# Power_Supply_Board.net
KiCad netlist of a schematic drawn in EasyEDA Pro
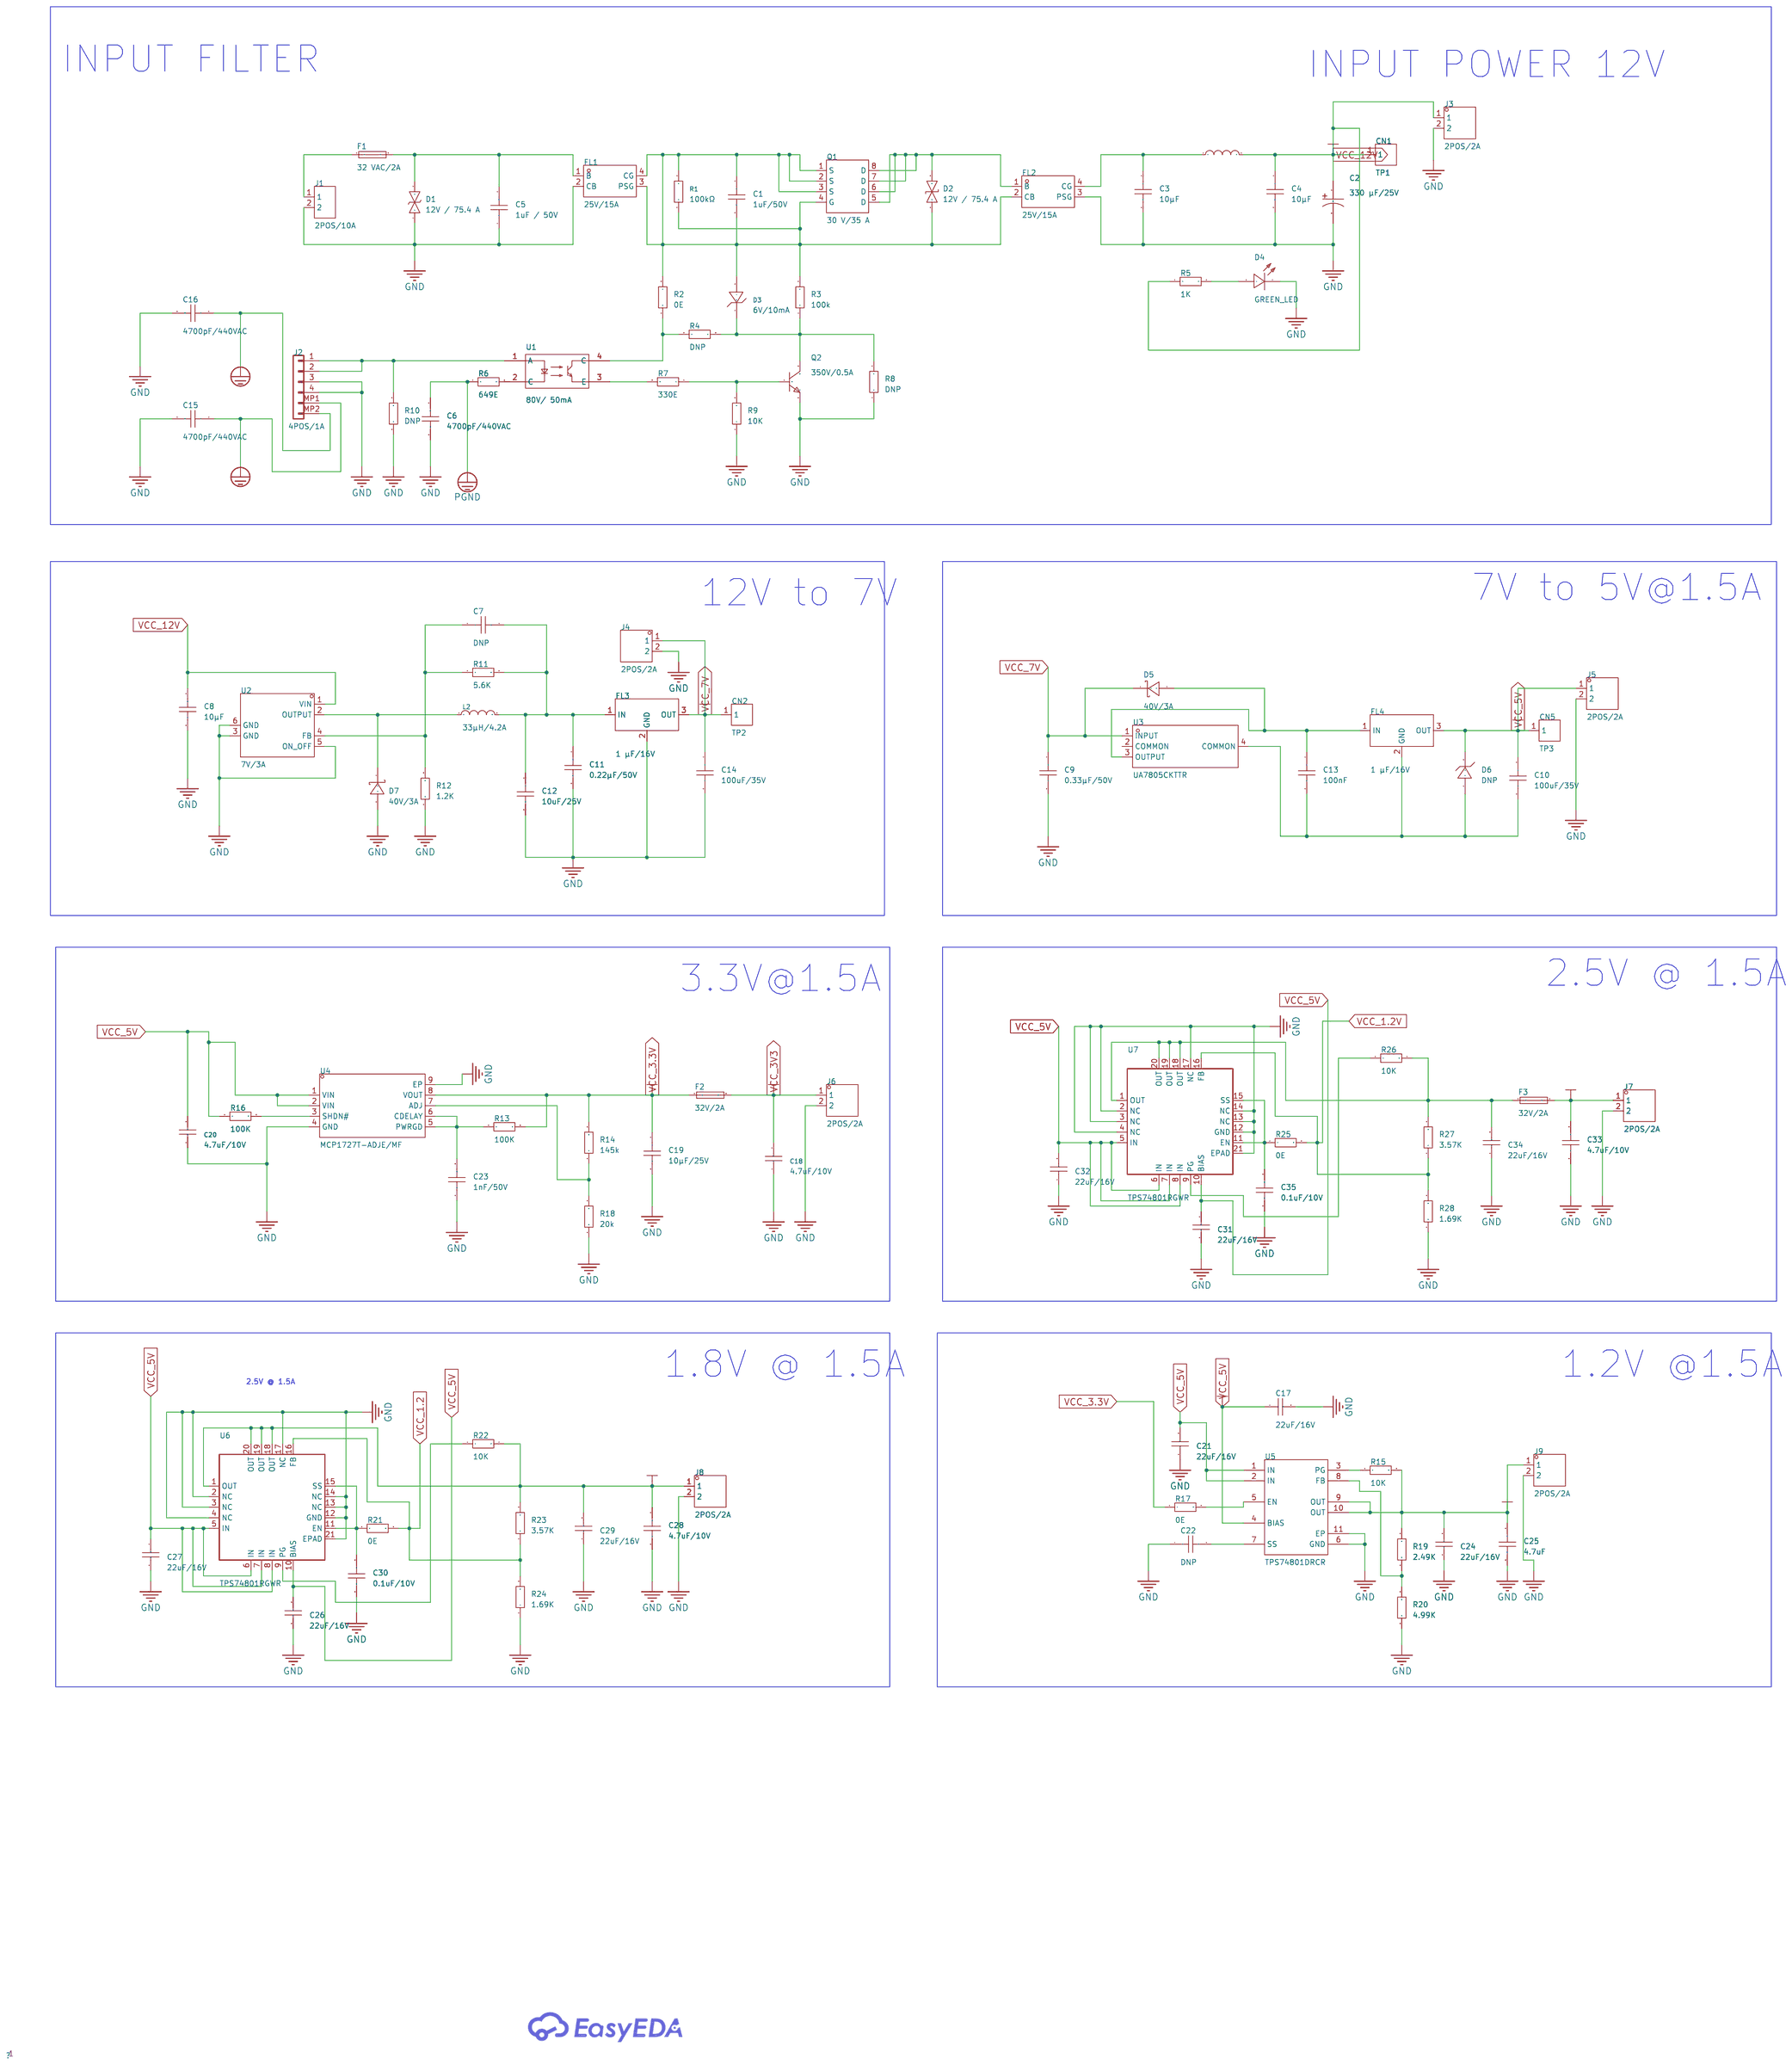
[diagram p0: schematic sheet]

(export (version "E")
  (design (tool "Eeschema 10.0.6"))
  (components
    (comp (ref "C1")
      (value "1uF/50V")
      (footprint "easyedapro:C0603")
      (libsource (lib "easyedapro") (part "CAP"))
    )
    (comp (ref "C2")
      (value "330 µF/25V")
      (footprint "easyedapro:CAP-SMD_BD10.0-L10.3-W10.3-FD")
      (fields (field (name "Manufacturer Part") "EEHZA1E331P") (field (name "Manufacturer") "PANASONIC(松下)"))
      (libsource (lib "easyedapro") (part "EEHZA1E331P"))
    )
    (comp (ref "C3")
      (value "10µF")
      (footprint "easyedapro:C0603")
      (libsource (lib "easyedapro") (part "CAP"))
    )
    (comp (ref "C4")
      (value "10µF")
      (footprint "easyedapro:C0603")
      (libsource (lib "easyedapro") (part "CAP"))
    )
    (comp (ref "C5")
      (value "1uF / 50V")
      (footprint "easyedapro:C0402")
      (description "Capacitance:100nF Tolerance:±10% Tolerance:±10% Voltage Rating:16V Temperature Coefficient:X7R")
      (fields
        (field (name "Manufacturer Part") "CL05B104KO5NNNC")
        (field (name "Manufacturer") "SAMSUNG(三星)")
      )
      (libsource (lib "easyedapro") (part "CL05B104KO5NNNC"))
    )
    (comp (ref "C6")
      (value "4700pF/440VAC")
      (footprint "easyedapro:CAP-TH_L11.0-W5.0-P10.00-D0.7")
      (fields
        (field (name "Manufacturer Part") "C947U472MZVDBA7317")
        (field (name "Manufacturer") "KEMET(基美)")
      )
      (libsource (lib "easyedapro") (part "C947U472MZVDBA7317"))
    )
    (comp (ref "C7") (value "DNP") (footprint "easyedapro:C0603") (libsource (lib "easyedapro") (part "CAP")))
    (comp (ref "C8")
      (value "10µF")
      (footprint "easyedapro:C0603")
      (libsource (lib "easyedapro") (part "CAP"))
    )
    (comp (ref "C9")
      (value "0.33µF/50V")
      (footprint "easyedapro:C0603")
      (libsource (lib "easyedapro") (part "CAP"))
    )
    (comp (ref "C10")
      (value "100uF/35V")
      (footprint "easyedapro:C0603")
      (libsource (lib "easyedapro") (part "CAP"))
    )
    (comp (ref "C11")
      (value "0.22µF/50V")
      (footprint "easyedapro:C0603")
      (libsource (lib "easyedapro") (part "CAP"))
    )
    (comp (ref "C12")
      (value "10uF/25V")
      (footprint "easyedapro:C0603")
      (libsource (lib "easyedapro") (part "CAP"))
    )
    (comp (ref "C13")
      (value "100nF")
      (footprint "easyedapro:C0603")
      (libsource (lib "easyedapro") (part "CAP"))
    )
    (comp (ref "C14")
      (value "100uF/35V")
      (footprint "easyedapro:C0603")
      (libsource (lib "easyedapro") (part "CAP"))
    )
    (comp (ref "C15")
      (value "4700pF/440VAC")
      (footprint "easyedapro:C0603")
      (libsource (lib "easyedapro") (part "CAP"))
    )
    (comp (ref "C16")
      (value "4700pF/440VAC")
      (footprint "easyedapro:C0603")
      (libsource (lib "easyedapro") (part "CAP"))
    )
    (comp (ref "C17")
      (value "22uF/16V")
      (footprint "easyedapro:C0805")
      (description "容值:22uF;精度:±20%;额定电压:16V;材质(温度系数):X5R;")
      (fields
        (field (name "Manufacturer Part") "CL21A226MOQNNNE")
        (field (name "Manufacturer") "SAMSUNG(三星)")
      )
      (libsource (lib "easyedapro") (part "CL21A226MOQNNNE"))
    )
    (comp (ref "C18")
      (value "4.7uF/10V")
      (footprint "easyedapro:C0603")
      (description "Capacitance:4.7uF Tolerance:±10% Tolerance:±10% Voltage Rating:10V Temperature Coefficient:X5R")
      (fields
        (field (name "Manufacturer Part") "CL10A475KP8NNNC")
        (field (name "Manufacturer") "SAMSUNG(三星)")
      )
      (libsource (lib "easyedapro") (part "CL10A475KP8NNNC"))
    )
    (comp (ref "C19")
      (value "10µF/25V")
      (footprint "easyedapro:C0603")
      (libsource (lib "easyedapro") (part "CAP"))
    )
    (comp (ref "C20")
      (value "4.7uF/10V")
      (footprint "easyedapro:C0603")
      (description "Capacitance:4.7uF Tolerance:±10% Tolerance:±10% Voltage Rating:10V Temperature Coefficient:X5R")
      (fields
        (field (name "Manufacturer Part") "CL10A475KP8NNNC")
        (field (name "Manufacturer") "SAMSUNG(三星)")
      )
      (libsource (lib "easyedapro") (part "CL10A475KP8NNNC"))
    )
    (comp (ref "C21")
      (value "22uF/16V")
      (footprint "easyedapro:C0805")
      (description "容值:22uF;精度:±20%;额定电压:16V;材质(温度系数):X5R;")
      (fields
        (field (name "Manufacturer Part") "CL21A226MOQNNNE")
        (field (name "Manufacturer") "SAMSUNG(三星)")
      )
      (libsource (lib "easyedapro") (part "CL21A226MOQNNNE"))
    )
    (comp (ref "C22")
      (value "DNP")
      (footprint "easyedapro:C0402")
      (fields
        (field (name "Manufacturer Part") "CC0402JRX7R6BB104")
        (field (name "Manufacturer") "YAGEO(国巨)")
      )
      (libsource (lib "easyedapro") (part "CC0402JRX7R6BB104"))
    )
    (comp (ref "C23")
      (value "1nF/50V")
      (footprint "easyedapro:C0402")
      (description "Capacitance:1nF Tolerance:±5% Tolerance:±5% Voltage Rating:50V Temperature Coefficient:C0G")
      (fields
        (field (name "Manufacturer Part") "GRM1555C1H102JA01D")
        (field (name "Manufacturer") "muRata(村田)")
      )
      (libsource (lib "easyedapro") (part "GRM1555C1H102JA01D"))
    )
    (comp (ref "C24")
      (value "22uF/16V")
      (footprint "easyedapro:C0805")
      (description "容值:22uF;精度:±20%;额定电压:16V;材质(温度系数):X5R;")
      (fields
        (field (name "Manufacturer Part") "CL21A226MOQNNNE")
        (field (name "Manufacturer") "SAMSUNG(三星)")
      )
      (libsource (lib "easyedapro") (part "CL21A226MOQNNNE"))
    )
    (comp (ref "C25")
      (value "4.7uF")
      (footprint "easyedapro:C0603")
      (libsource (lib "easyedapro") (part "CAP"))
    )
    (comp (ref "C26")
      (value "22uF/16V")
      (footprint "easyedapro:C0805")
      (description "容值:22uF;精度:±20%;额定电压:16V;材质(温度系数):X5R;")
      (fields
        (field (name "Manufacturer Part") "CL21A226MOQNNNE")
        (field (name "Manufacturer") "SAMSUNG(三星)")
      )
      (libsource (lib "easyedapro") (part "CL21A226MOQNNNE"))
    )
    (comp (ref "C27")
      (value "22uF/16V")
      (footprint "easyedapro:C0805")
      (description "容值:22uF;精度:±20%;额定电压:16V;材质(温度系数):X5R;")
      (fields
        (field (name "Manufacturer Part") "CL21A226MOQNNNE")
        (field (name "Manufacturer") "SAMSUNG(三星)")
      )
      (libsource (lib "easyedapro") (part "CL21A226MOQNNNE"))
    )
    (comp (ref "C28")
      (value "4.7uF/10V")
      (footprint "easyedapro:C0603")
      (libsource (lib "easyedapro") (part "CAP"))
    )
    (comp (ref "C29")
      (value "22uF/16V")
      (footprint "easyedapro:C0805")
      (description "容值:22uF;精度:±20%;额定电压:16V;材质(温度系数):X5R;")
      (fields
        (field (name "Manufacturer Part") "CL21A226MOQNNNE")
        (field (name "Manufacturer") "SAMSUNG(三星)")
      )
      (libsource (lib "easyedapro") (part "CL21A226MOQNNNE"))
    )
    (comp (ref "C30")
      (value "0.1uF/10V")
      (footprint "easyedapro:C0402")
      (fields
        (field (name "Manufacturer Part") "CC0402JRX7R6BB104")
        (field (name "Manufacturer") "YAGEO(国巨)")
      )
      (libsource (lib "easyedapro") (part "CC0402JRX7R6BB104"))
    )
    (comp (ref "C31")
      (value "22uF/16V")
      (footprint "easyedapro:C0805")
      (description "容值:22uF;精度:±20%;额定电压:16V;材质(温度系数):X5R;")
      (fields
        (field (name "Manufacturer Part") "CL21A226MOQNNNE")
        (field (name "Manufacturer") "SAMSUNG(三星)")
      )
      (libsource (lib "easyedapro") (part "CL21A226MOQNNNE"))
    )
    (comp (ref "C32")
      (value "22uF/16V")
      (footprint "easyedapro:C0805")
      (description "容值:22uF;精度:±20%;额定电压:16V;材质(温度系数):X5R;")
      (fields
        (field (name "Manufacturer Part") "CL21A226MOQNNNE")
        (field (name "Manufacturer") "SAMSUNG(三星)")
      )
      (libsource (lib "easyedapro") (part "CL21A226MOQNNNE"))
    )
    (comp (ref "C33")
      (value "4.7uF/10V")
      (footprint "easyedapro:C0603")
      (libsource (lib "easyedapro") (part "CAP"))
    )
    (comp (ref "C34")
      (value "22uF/16V")
      (footprint "easyedapro:C0805")
      (description "容值:22uF;精度:±20%;额定电压:16V;材质(温度系数):X5R;")
      (fields
        (field (name "Manufacturer Part") "CL21A226MOQNNNE")
        (field (name "Manufacturer") "SAMSUNG(三星)")
      )
      (libsource (lib "easyedapro") (part "CL21A226MOQNNNE"))
    )
    (comp (ref "C35")
      (value "0.1uF/10V")
      (footprint "easyedapro:C0402")
      (fields
        (field (name "Manufacturer Part") "CC0402JRX7R6BB104")
        (field (name "Manufacturer") "YAGEO(国巨)")
      )
      (libsource (lib "easyedapro") (part "CC0402JRX7R6BB104"))
    )
    (comp (ref "CN1")
      (value "TP1")
      (footprint "easyedapro:CONN-SMD_5017")
      (libsource (lib "easyedapro") (part "5017_C9900015874"))
    )
    (comp (ref "CN2")
      (value "TP2")
      (footprint "easyedapro:CONN-SMD_5017")
      (libsource (lib "easyedapro") (part "5017_C9900015874"))
    )
    (comp (ref "CN5")
      (value "TP3")
      (footprint "easyedapro:CONN-SMD_5017")
      (libsource (lib "easyedapro") (part "5017_C9900015874"))
    )
    (comp (ref "D1")
      (value "12V / 75.4 A")
      (footprint "easyedapro:D0402-BI")
      (fields (field (name "Manufacturer") "GOOD-ARK(固锝)"))
      (libsource (lib "easyedapro") (part "GSEPD15B0005"))
    )
    (comp (ref "D2")
      (value "12V / 75.4 A")
      (footprint "easyedapro:SMC_L6.9-W5.9-LS7.9-BI")
      (fields (field (name "Manufacturer") "R+O(宏嘉诚)"))
      (libsource (lib "easyedapro") (part "SMCJ12CA_C41411748"))
    )
    (comp (ref "D3")
      (value "6V/10mA")
      (footprint "easyedapro:SOD-123_L2.7-W1.6-LS3.7-RD")
      (fields (field (name "Manufacturer") "onsemi(安森美)"))
      (libsource (lib "easyedapro") (part "MMSZ5233BT1G"))
    )
    (comp (ref "D4")
      (value "GREEN_LED")
      (footprint "easyedapro:LED0603-RD")
      (fields (field (name "Manufacturer") "LITEON(光宝)"))
      (libsource (lib "easyedapro") (part "LTST-C190KGKT"))
    )
    (comp (ref "D5")
      (value "40V/3A")
      (footprint "easyedapro:SOD-128_L3.7-W2.5-LS4.7-RD")
      (fields (field (name "Manufacturer") "Nexperia(安世)"))
      (libsource (lib "easyedapro") (part "PMEG40T30EPX"))
    )
    (comp (ref "D6")
      (value "DNP")
      (footprint "easyedapro:SOD-123_L2.8-W1.8-LS3.7-RD")
      (fields (field (name "Manufacturer") "DIODES(美台)"))
      (libsource (lib "easyedapro") (part "MMSZ5231B-7-F"))
    )
    (comp (ref "D7")
      (value "40V/3A")
      (footprint "easyedapro:SOD-128_L3.7-W2.5-LS4.7-RD")
      (fields (field (name "Manufacturer") "Nexperia(安世)"))
      (libsource (lib "easyedapro") (part "PMEG40T30EPX"))
    )
    (comp (ref "F1")
      (value "32 VAC/2A")
      (footprint "easyedapro:FUSE-SMD_L20.0-W5.2")
      (fields (field (name "Manufacturer") "SET(赛尔特)"))
      (libsource (lib "easyedapro") (part "FUSE SGT520-8A"))
    )
    (comp (ref "F2")
      (value "32V/2A")
      (footprint "easyedapro:F0402")
      (fields (field (name "Manufacturer") "PANASONIC(松下)"))
      (libsource (lib "easyedapro") (part "ERBRD2R00X"))
    )
    (comp (ref "F3")
      (value "32V/2A")
      (footprint "easyedapro:F0402")
      (fields (field (name "Manufacturer") "PANASONIC(松下)"))
      (libsource (lib "easyedapro") (part "ERBRD2R00X"))
    )
    (comp (ref "FL1")
      (value "25V/15A")
      (footprint "easyedapro:FILTER-TH_6P-L12.0-W11.0_BNX016-01")
      (fields (field (name "Manufacturer Part") "BNX016-01") (field (name "Manufacturer") "muRata(村田)"))
      (libsource (lib "easyedapro") (part "BNX016-01"))
    )
    (comp (ref "FL2")
      (value "25V/15A")
      (footprint "easyedapro:FILTER-TH_6P-L12.0-W11.0_BNX016-01")
      (fields (field (name "Manufacturer Part") "BNX016-01") (field (name "Manufacturer") "muRata(村田)"))
      (libsource (lib "easyedapro") (part "BNX016-01"))
    )
    (comp (ref "FL3")
      (value "1 µF/16V")
      (footprint "easyedapro:FILTER-SMD_3P-L2.0-W1.2-L")
      (fields (field (name "Manufacturer") "muRata(村田)"))
      (libsource (lib "easyedapro") (part "NFM21PC105B1C3D"))
    )
    (comp (ref "FL4")
      (value "1 µF/16V")
      (footprint "easyedapro:FILTER-SMD_3P-L2.0-W1.2-L")
      (fields (field (name "Manufacturer") "muRata(村田)"))
      (libsource (lib "easyedapro") (part "NFM21PC105B1C3D"))
    )
    (comp (ref "J1")
      (value "2POS/10A")
      (footprint "easyedapro:CONN-TH_2P-P3.96-V")
      (fields (field (name "Manufacturer") "JST"))
      (libsource (lib "easyedapro") (part "B2P-VH-GZ"))
    )
    (comp (ref "J2")
      (value "Molex_PicoBlade_1x4_0533980471")
      (footprint "easyedapro:antmicro-footprints:Conn_Molex_PicoBlade_1x4_0533980471")
      (libsource (lib "easyedapro") (part "antmicroWire2BoardConnectors_Molex_PicoBlade_1x4_0533980471"))
    )
    (comp (ref "J3")
      (value "2POS/2A")
      (footprint "easyedapro:CONN-TH_S2B-PH-K-S-GW")
      (fields (field (name "Manufacturer") "JST"))
      (libsource (lib "easyedapro") (part "S2B-PH-K-S-GW"))
    )
    (comp (ref "J4")
      (value "2POS/2A")
      (footprint "easyedapro:CONN-TH_S2B-PH-K-S-GW")
      (fields (field (name "Manufacturer") "JST"))
      (libsource (lib "easyedapro") (part "S2B-PH-K-S-GW"))
    )
    (comp (ref "J5")
      (value "2POS/2A")
      (footprint "easyedapro:CONN-TH_S2B-PH-K-S-GW")
      (fields (field (name "Manufacturer") "JST"))
      (libsource (lib "easyedapro") (part "S2B-PH-K-S-GW"))
    )
    (comp (ref "J6")
      (value "2POS/2A")
      (footprint "easyedapro:CONN-TH_S2B-PH-K-S-GW")
      (fields (field (name "Manufacturer") "JST"))
      (libsource (lib "easyedapro") (part "S2B-PH-K-S-GW"))
    )
    (comp (ref "J7")
      (value "2POS/2A")
      (footprint "easyedapro:CONN-TH_S2B-PH-K-S-GW")
      (fields (field (name "Manufacturer") "JST"))
      (libsource (lib "easyedapro") (part "S2B-PH-K-S-GW"))
    )
    (comp (ref "J8")
      (value "2POS/2A")
      (footprint "easyedapro:CONN-TH_S2B-PH-K-S-GW")
      (fields (field (name "Manufacturer") "JST"))
      (libsource (lib "easyedapro") (part "S2B-PH-K-S-GW"))
    )
    (comp (ref "J9")
      (value "2POS/2A")
      (footprint "easyedapro:CONN-TH_S2B-PH-K-S-GW")
      (fields (field (name "Manufacturer") "JST"))
      (libsource (lib "easyedapro") (part "S2B-PH-K-S-GW"))
    )
    (comp (ref "L1")
      (value "22uH")
      (footprint "easyedapro:7447709220")
      (fields (field (name "Manufacturer Part") "22µH/5.3A") (field (name "Manufacturer") "WURTH"))
      (libsource (lib "easyedapro") (part "7447709220"))
    )
    (comp (ref "L2")
      (value "33µH/4.2A")
      (footprint "easyedapro:IND-SMD_L12.0-W12.0-A")
      (fields (field (name "Manufacturer Part") "7447709330") (field (name "Manufacturer") "Wurth(伍尔特)"))
      (libsource (lib "easyedapro") (part "7447709330"))
    )
    (comp (ref "Q1")
      (value "30 V/35 A")
      (footprint "easyedapro:POWERPAK-1212-8_L3.0-W3.0-P0.65-LS3.3-BL")
      (fields (field (name "Manufacturer") "MSKSEMI(美森科)"))
      (libsource (lib "easyedapro") (part "MSISH101DN-T1-GE3"))
    )
    (comp (ref "Q2")
      (value "350V/0.5A")
      (footprint "easyedapro:SOT-23-3_L2.9-W1.3-P1.90-LS2.4-BR")
      (fields (field (name "Manufacturer") "DIODES(美台)"))
      (libsource (lib "easyedapro") (part "FMMT6517TA"))
    )
    (comp (ref "R1")
      (value "100kΩ")
      (footprint "easyedapro:R0603")
      (fields (field (name "Manufacturer Part") "RC0603FR-07100KL") (field (name "Manufacturer") "YAGEO(国巨)"))
      (libsource (lib "easyedapro") (part "RC0603FR-07100KL"))
    )
    (comp (ref "R2") (value "0E") (footprint "easyedapro:R0603") (libsource (lib "easyedapro") (part "Res")))
    (comp (ref "R3")
      (value "100k")
      (footprint "easyedapro:R0603")
      (libsource (lib "easyedapro") (part "Res"))
    )
    (comp (ref "R4") (value "DNP") (footprint "easyedapro:R0603") (libsource (lib "easyedapro") (part "Res")))
    (comp (ref "R5") (value "1K") (footprint "easyedapro:R0603") (libsource (lib "easyedapro") (part "Res")))
    (comp (ref "R6")
      (value "649E")
      (footprint "easyedapro:R0603")
      (libsource (lib "easyedapro") (part "Res"))
    )
    (comp (ref "R7")
      (value "330E")
      (footprint "easyedapro:R0603")
      (libsource (lib "easyedapro") (part "Res"))
    )
    (comp (ref "R8") (value "DNP") (footprint "easyedapro:R0603") (libsource (lib "easyedapro") (part "Res")))
    (comp (ref "R9") (value "10K") (footprint "easyedapro:R0603") (libsource (lib "easyedapro") (part "Res")))
    (comp (ref "R10")
      (value "DNP")
      (footprint "easyedapro:R0603")
      (libsource (lib "easyedapro") (part "Res"))
    )
    (comp (ref "R11")
      (value "5.6K")
      (footprint "easyedapro:R0603")
      (libsource (lib "easyedapro") (part "Res"))
    )
    (comp (ref "R12")
      (value "1.2K")
      (footprint "easyedapro:R0603")
      (libsource (lib "easyedapro") (part "Res"))
    )
    (comp (ref "R13")
      (value "100K")
      (footprint "easyedapro:R0402")
      (fields (field (name "Manufacturer Part") "ERJ2RKF1003X") (field (name "Manufacturer") "PANASONIC(松下)"))
      (libsource (lib "easyedapro") (part "ERJ-2RKF1003X"))
    )
    (comp (ref "R14")
      (value "145k")
      (footprint "easyedapro:R0603")
      (libsource (lib "easyedapro") (part "Res"))
    )
    (comp (ref "R15")
      (value "10K")
      (footprint "easyedapro:R0603")
      (libsource (lib "easyedapro") (part "Res"))
    )
    (comp (ref "R16")
      (value "100K")
      (footprint "easyedapro:R0402")
      (fields (field (name "Manufacturer Part") "ERJ2RKF1003X") (field (name "Manufacturer") "PANASONIC(松下)"))
      (libsource (lib "easyedapro") (part "ERJ-2RKF1003X"))
    )
    (comp (ref "R17") (value "0E") (footprint "easyedapro:R0603") (libsource (lib "easyedapro") (part "Res")))
    (comp (ref "R18")
      (value "20k")
      (footprint "easyedapro:R0603")
      (libsource (lib "easyedapro") (part "Res"))
    )
    (comp (ref "R19")
      (value "2.49K")
      (footprint "easyedapro:R0603")
      (libsource (lib "easyedapro") (part "Res"))
    )
    (comp (ref "R20")
      (value "4.99K")
      (footprint "easyedapro:R0603")
      (libsource (lib "easyedapro") (part "Res"))
    )
    (comp (ref "R21") (value "0E") (footprint "easyedapro:R0603") (libsource (lib "easyedapro") (part "Res")))
    (comp (ref "R22")
      (value "10K")
      (footprint "easyedapro:R0603")
      (libsource (lib "easyedapro") (part "Res"))
    )
    (comp (ref "R23")
      (value "3.57K")
      (footprint "easyedapro:R0603")
      (libsource (lib "easyedapro") (part "Res"))
    )
    (comp (ref "R24")
      (value "1.69K")
      (footprint "easyedapro:R0603")
      (libsource (lib "easyedapro") (part "Res"))
    )
    (comp (ref "R25") (value "0E") (footprint "easyedapro:R0603") (libsource (lib "easyedapro") (part "Res")))
    (comp (ref "R26")
      (value "10K")
      (footprint "easyedapro:R0603")
      (libsource (lib "easyedapro") (part "Res"))
    )
    (comp (ref "R27")
      (value "3.57K")
      (footprint "easyedapro:R0603")
      (libsource (lib "easyedapro") (part "Res"))
    )
    (comp (ref "R28")
      (value "1.69K")
      (footprint "easyedapro:R0603")
      (libsource (lib "easyedapro") (part "Res"))
    )
    (comp (ref "U1")
      (value "80V/ 50mA")
      (footprint "easyedapro:SOP-4_L6.5-W4.6-P2.54-LS10.3-TL")
      (fields (field (name "Manufacturer") "VISHAY(威世)"))
      (libsource (lib "easyedapro") (part "VO617A-8X017T"))
    )
    (comp (ref "U2")
      (value "7V/3A")
      (footprint "easyedapro:TO-263-5_L10.4-W8.6-P1.70-LS15.3-BR")
      (libsource (lib "easyedapro") (part "LM2596S-ADJ_C3198435"))
    )
    (comp (ref "U3")
      (value "UA7805CKTTR")
      (footprint "easyedapro:TO-263-3_L10.2-W9.0-P2.54-LS15.2-TL")
      (fields (field (name "Manufacturer") "TI(德州仪器)"))
      (libsource (lib "easyedapro") (part "UA7805CKTTR"))
    )
    (comp (ref "U4")
      (value "MCP1727T-ADJE/MF")
      (footprint "easyedapro:DFN-8_L3.0-W3.0-P0.65-BL-EP")
      (fields (field (name "Manufacturer") "MICROCHIP(美国微芯)"))
      (libsource (lib "easyedapro") (part "MCP1727T-ADJE/MF"))
    )
    (comp (ref "U5")
      (value "TPS74801DRCR")
      (footprint "easyedapro:VSON-10_L3.0-W3.0-P0.50-TL-EP")
      (fields (field (name "Manufacturer") "TI(德州仪器)"))
      (libsource (lib "easyedapro") (part "TPS74801DRCR"))
    )
    (comp (ref "U6")
      (value "TPS74801RGWR")
      (footprint "easyedapro:VQFN-20_L5.0-W5.0-P0.65-TL-EP")
      (fields (field (name "Manufacturer") "Texas Instruments"))
      (libsource (lib "easyedapro") (part "TPS74801RGWR"))
    )
    (comp (ref "U7")
      (value "TPS74801RGWR")
      (footprint "easyedapro:VQFN-20_L5.0-W5.0-P0.65-TL-EP")
      (fields (field (name "Manufacturer") "Texas Instruments"))
      (libsource (lib "easyedapro") (part "TPS74801RGWR"))
    )
  )
  (nets
    (net (code "1") (name "GND") (class "Default")
      (node (ref "C11") (pin "2") (pinfunction "2_2") (pintype "input"))
      (node (ref "C12") (pin "2") (pinfunction "2_2") (pintype "input"))
      (node (ref "C14") (pin "2") (pinfunction "2_2") (pintype "input"))
      (node (ref "C15") (pin "2") (pinfunction "2_2") (pintype "input"))
      (node (ref "C16") (pin "2") (pinfunction "2_2") (pintype "input"))
      (node (ref "C17") (pin "2") (pinfunction "2_2") (pintype "input"))
      (node (ref "C18") (pin "1") (pinfunction "1_1") (pintype "input"))
      (node (ref "C19") (pin "2") (pinfunction "2_2") (pintype "input"))
      (node (ref "C2") (pin "2") (pinfunction "2_2") (pintype "unspecified"))
      (node (ref "C20") (pin "1") (pinfunction "1_1") (pintype "input"))
      (node (ref "C21") (pin "1") (pinfunction "1_1") (pintype "input"))
      (node (ref "C22") (pin "1") (pinfunction "1_1") (pintype "input"))
      (node (ref "C23") (pin "1") (pinfunction "1_1") (pintype "unspecified"))
      (node (ref "C24") (pin "1") (pinfunction "1_1") (pintype "input"))
      (node (ref "C25") (pin "2") (pinfunction "2_2") (pintype "input"))
      (node (ref "C26") (pin "1") (pinfunction "1_1") (pintype "input"))
      (node (ref "C27") (pin "1") (pinfunction "1_1") (pintype "input"))
      (node (ref "C28") (pin "2") (pinfunction "2_2") (pintype "input"))
      (node (ref "C29") (pin "1") (pinfunction "1_1") (pintype "input"))
      (node (ref "C3") (pin "2") (pinfunction "2_2") (pintype "input"))
      (node (ref "C30") (pin "1") (pinfunction "1_1") (pintype "input"))
      (node (ref "C31") (pin "1") (pinfunction "1_1") (pintype "input"))
      (node (ref "C32") (pin "1") (pinfunction "1_1") (pintype "input"))
      (node (ref "C33") (pin "2") (pinfunction "2_2") (pintype "input"))
      (node (ref "C34") (pin "1") (pinfunction "1_1") (pintype "input"))
      (node (ref "C35") (pin "1") (pinfunction "1_1") (pintype "input"))
      (node (ref "C4") (pin "2") (pinfunction "2_2") (pintype "input"))
      (node (ref "C5") (pin "1") (pinfunction "1_1") (pintype "unspecified"))
      (node (ref "C6") (pin "1") (pinfunction "1_1") (pintype "unspecified"))
      (node (ref "C8") (pin "2") (pinfunction "2_2") (pintype "input"))
      (node (ref "C9") (pin "2") (pinfunction "2_2") (pintype "input"))
      (node (ref "D1") (pin "1") (pinfunction "1_1") (pintype "unspecified"))
      (node (ref "D4") (pin "1") (pinfunction "-_1") (pintype "unspecified"))
      (node (ref "D7") (pin "2") (pinfunction "A_2") (pintype "unspecified"))
      (node (ref "FL1") (pin "2") (pinfunction "CB_2") (pintype "input"))
      (node (ref "FL2") (pin "3") (pinfunction "PSG_3") (pintype "input"))
      (node (ref "FL3") (pin "2") (pinfunction "GND_2") (pintype "unspecified"))
      (node (ref "J1") (pin "2") (pinfunction "2_2") (pintype "unspecified"))
      (node (ref "J2") (pin "3") (pinfunction "3_3") (pintype "unspecified"))
      (node (ref "J2") (pin "4") (pinfunction "4_4") (pintype "unspecified"))
      (node (ref "J3") (pin "2") (pinfunction "2_2") (pintype "unspecified"))
      (node (ref "J4") (pin "2") (pinfunction "2_2") (pintype "unspecified"))
      (node (ref "J5") (pin "2") (pinfunction "2_2") (pintype "unspecified"))
      (node (ref "J6") (pin "2") (pinfunction "2_2") (pintype "unspecified"))
      (node (ref "J7") (pin "2") (pinfunction "2_2") (pintype "unspecified"))
      (node (ref "J8") (pin "2") (pinfunction "2_2") (pintype "unspecified"))
      (node (ref "J9") (pin "2") (pinfunction "2_2") (pintype "unspecified"))
      (node (ref "Q2") (pin "2") (pinfunction "E_2") (pintype "unspecified"))
      (node (ref "R10") (pin "1") (pinfunction "1_1") (pintype "input"))
      (node (ref "R12") (pin "1") (pinfunction "1_1") (pintype "input"))
      (node (ref "R18") (pin "1") (pinfunction "1_1") (pintype "input"))
      (node (ref "R20") (pin "1") (pinfunction "1_1") (pintype "input"))
      (node (ref "R24") (pin "1") (pinfunction "1_1") (pintype "input"))
      (node (ref "R28") (pin "1") (pinfunction "1_1") (pintype "input"))
      (node (ref "R8") (pin "1") (pinfunction "1_1") (pintype "input"))
      (node (ref "R9") (pin "1") (pinfunction "1_1") (pintype "input"))
      (node (ref "U2") (pin "3") (pinfunction "GND_3") (pintype "unspecified"))
      (node (ref "U2") (pin "5") (pinfunction "ON_OFF_5") (pintype "unspecified"))
      (node (ref "U2") (pin "6") (pinfunction "GND_6") (pintype "unspecified"))
      (node (ref "U4") (pin "4") (pinfunction "GND_4") (pintype "unspecified"))
      (node (ref "U4") (pin "9") (pinfunction "EP_9") (pintype "unspecified"))
      (node (ref "U5") (pin "11") (pinfunction "EP_11") (pintype "unspecified"))
      (node (ref "U5") (pin "6") (pinfunction "GND_6") (pintype "unspecified"))
      (node (ref "U6") (pin "12") (pinfunction "GND_12") (pintype "unspecified"))
      (node (ref "U6") (pin "13") (pinfunction "NC_13") (pintype "unspecified"))
      (node (ref "U6") (pin "14") (pinfunction "NC_14") (pintype "unspecified"))
      (node (ref "U6") (pin "17") (pinfunction "NC_17") (pintype "unspecified"))
      (node (ref "U6") (pin "2") (pinfunction "NC_2") (pintype "unspecified"))
      (node (ref "U6") (pin "21") (pinfunction "EPAD_21") (pintype "unspecified"))
      (node (ref "U6") (pin "3") (pinfunction "NC_3") (pintype "unspecified"))
      (node (ref "U6") (pin "4") (pinfunction "NC_4") (pintype "unspecified"))
      (node (ref "U7") (pin "12") (pinfunction "GND_12") (pintype "unspecified"))
      (node (ref "U7") (pin "13") (pinfunction "NC_13") (pintype "unspecified"))
      (node (ref "U7") (pin "14") (pinfunction "NC_14") (pintype "unspecified"))
      (node (ref "U7") (pin "17") (pinfunction "NC_17") (pintype "unspecified"))
      (node (ref "U7") (pin "2") (pinfunction "NC_2") (pintype "unspecified"))
      (node (ref "U7") (pin "21") (pinfunction "EPAD_21") (pintype "unspecified"))
      (node (ref "U7") (pin "3") (pinfunction "NC_3") (pintype "unspecified"))
      (node (ref "U7") (pin "4") (pinfunction "NC_4") (pintype "unspecified"))
    )
    (net (code "2") (name "ISO_GND") (class "Default")
      (node (ref "C15") (pin "1") (pinfunction "1_1") (pintype "input"))
      (node (ref "C16") (pin "1") (pinfunction "1_1") (pintype "input"))
      (node (ref "J2") (pin "MP1") (pinfunction "MP1_MP1") (pintype "unspecified"))
      (node (ref "J2") (pin "MP2") (pinfunction "MP2_MP2") (pintype "unspecified"))
    )
    (net (code "3") (name "Net-(C34-Pad2)") (class "Default")
      (node (ref "C34") (pin "2") (pinfunction "2_2") (pintype "input"))
      (node (ref "F3") (pin "1") (pinfunction "1_1") (pintype "input"))
      (node (ref "R26") (pin "2") (pinfunction "2_2") (pintype "input"))
      (node (ref "R27") (pin "2") (pinfunction "2_2") (pintype "input"))
      (node (ref "U7") (pin "1") (pinfunction "OUT_1") (pintype "unspecified"))
      (node (ref "U7") (pin "18") (pinfunction "OUT_18") (pintype "unspecified"))
      (node (ref "U7") (pin "19") (pinfunction "OUT_19") (pintype "unspecified"))
      (node (ref "U7") (pin "20") (pinfunction "OUT_20") (pintype "unspecified"))
    )
    (net (code "4") (name "Net-(D3-A)") (class "Default")
      (node (ref "C1") (pin "1") (pinfunction "1_1") (pintype "input"))
      (node (ref "C1") (pin "2") (pinfunction "2_2") (pintype "input"))
      (node (ref "D2") (pin "1") (pinfunction "1_1") (pintype "unspecified"))
      (node (ref "D3") (pin "2") (pinfunction "A_2") (pintype "input"))
      (node (ref "FL1") (pin "3") (pinfunction "PSG_3") (pintype "input"))
      (node (ref "FL1") (pin "4") (pinfunction "CG_4") (pintype "input"))
      (node (ref "FL2") (pin "2") (pinfunction "CB_2") (pintype "input"))
      (node (ref "Q1") (pin "1") (pinfunction "S_1") (pintype "unspecified"))
      (node (ref "Q1") (pin "2") (pinfunction "S_2") (pintype "unspecified"))
      (node (ref "Q1") (pin "3") (pinfunction "S_3") (pintype "unspecified"))
      (node (ref "Q1") (pin "4") (pinfunction "G_4") (pintype "unspecified"))
      (node (ref "R1") (pin "1") (pinfunction "1_1") (pintype "input"))
      (node (ref "R1") (pin "2") (pinfunction "2_2") (pintype "input"))
      (node (ref "R2") (pin "2") (pinfunction "2_2") (pintype "input"))
      (node (ref "R3") (pin "2") (pinfunction "2_2") (pintype "input"))
    )
    (net (code "5") (name "Net-(D3-C)") (class "Default")
      (node (ref "D3") (pin "1") (pinfunction "C_1") (pintype "input"))
      (node (ref "Q2") (pin "3") (pinfunction "C_3") (pintype "unspecified"))
      (node (ref "R3") (pin "1") (pinfunction "1_1") (pintype "input"))
      (node (ref "R4") (pin "2") (pinfunction "2_2") (pintype "input"))
      (node (ref "R8") (pin "2") (pinfunction "2_2") (pintype "input"))
    )
    (net (code "6") (name "Net-(D4-+)") (class "Default")
      (node (ref "D4") (pin "2") (pinfunction "+_2") (pintype "unspecified"))
      (node (ref "R5") (pin "2") (pinfunction "2_2") (pintype "input"))
    )
    (net (code "7") (name "Net-(D5-A)") (class "Default")
      (node (ref "C13") (pin "1") (pinfunction "1_1") (pintype "input"))
      (node (ref "D5") (pin "2") (pinfunction "A_2") (pintype "unspecified"))
      (node (ref "FL4") (pin "1") (pinfunction "IN_1") (pintype "unspecified"))
      (node (ref "U3") (pin "3") (pinfunction "OUTPUT_3") (pintype "unspecified"))
    )
    (net (code "8") (name "Net-(D6-A)") (class "Default")
      (node (ref "C10") (pin "2") (pinfunction "2_2") (pintype "input"))
      (node (ref "C13") (pin "2") (pinfunction "2_2") (pintype "input"))
      (node (ref "D6") (pin "2") (pinfunction "A_2") (pintype "input"))
      (node (ref "FL4") (pin "2") (pinfunction "GND_2") (pintype "unspecified"))
      (node (ref "U3") (pin "4") (pinfunction "COMMON_4") (pintype "unspecified"))
    )
    (net (code "9") (name "Net-(D7-C)") (class "Default")
      (node (ref "D7") (pin "1") (pinfunction "C_1") (pintype "unspecified"))
      (node (ref "L2") (pin "1") (pinfunction "1_1") (pintype "input"))
      (node (ref "U2") (pin "2") (pinfunction "OUTPUT_2") (pintype "unspecified"))
    )
    (net (code "10") (name "Net-(F1-Pad1)") (class "Default")
      (node (ref "F1") (pin "1") (pinfunction "1_1") (pintype "unspecified"))
      (node (ref "J1") (pin "1") (pinfunction "1_1") (pintype "unspecified"))
    )
    (net (code "11") (name "Net-(FL1-B)") (class "Default")
      (node (ref "C5") (pin "2") (pinfunction "2_2") (pintype "unspecified"))
      (node (ref "D1") (pin "2") (pinfunction "2_2") (pintype "unspecified"))
      (node (ref "F1") (pin "2") (pinfunction "2_2") (pintype "unspecified"))
      (node (ref "FL1") (pin "1") (pinfunction "B_1") (pintype "input"))
    )
    (net (code "12") (name "Net-(FL2-B)") (class "Default")
      (node (ref "D2") (pin "2") (pinfunction "2_2") (pintype "unspecified"))
      (node (ref "FL2") (pin "1") (pinfunction "B_1") (pintype "input"))
      (node (ref "Q1") (pin "5") (pinfunction "D_5") (pintype "unspecified"))
      (node (ref "Q1") (pin "6") (pinfunction "D_6") (pintype "unspecified"))
      (node (ref "Q1") (pin "7") (pinfunction "D_7") (pintype "unspecified"))
      (node (ref "Q1") (pin "8") (pinfunction "D_8") (pintype "unspecified"))
    )
    (net (code "13") (name "Net-(FL2-CG)") (class "Default")
      (node (ref "C3") (pin "1") (pinfunction "1_1") (pintype "input"))
      (node (ref "FL2") (pin "4") (pinfunction "CG_4") (pintype "input"))
      (node (ref "L1") (pin "1") (pinfunction "1_1") (pintype "unspecified"))
    )
    (net (code "14") (name "Net-(FL3-IN)") (class "Default")
      (node (ref "C11") (pin "1") (pinfunction "1_1") (pintype "input"))
      (node (ref "C12") (pin "1") (pinfunction "1_1") (pintype "input"))
      (node (ref "C7") (pin "1") (pinfunction "1_1") (pintype "input"))
      (node (ref "FL3") (pin "1") (pinfunction "IN_1") (pintype "unspecified"))
      (node (ref "L2") (pin "2") (pinfunction "2_2") (pintype "input"))
      (node (ref "R11") (pin "2") (pinfunction "2_2") (pintype "input"))
    )
    (net (code "15") (name "Net-(Q2-B)") (class "Default")
      (node (ref "Q2") (pin "1") (pinfunction "B_1") (pintype "unspecified"))
      (node (ref "R7") (pin "1") (pinfunction "1_1") (pintype "input"))
      (node (ref "R9") (pin "2") (pinfunction "2_2") (pintype "input"))
    )
    (net (code "16") (name "Net-(R2-Pad1)") (class "Default")
      (node (ref "R2") (pin "1") (pinfunction "1_1") (pintype "input"))
      (node (ref "R4") (pin "1") (pinfunction "1_1") (pintype "input"))
      (node (ref "U1") (pin "4") (pinfunction "C_4") (pintype "unspecified"))
    )
    (net (code "17") (name "Net-(R6-Pad2)") (class "Default")
      (node (ref "R6") (pin "2") (pinfunction "2_2") (pintype "input"))
      (node (ref "U1") (pin "2") (pinfunction "C_2") (pintype "unspecified"))
    )
    (net (code "18") (name "Net-(U1-A)") (class "Default")
      (node (ref "J2") (pin "1") (pinfunction "1_1") (pintype "unspecified"))
      (node (ref "J2") (pin "2") (pinfunction "2_2") (pintype "unspecified"))
      (node (ref "R10") (pin "2") (pinfunction "2_2") (pintype "input"))
      (node (ref "U1") (pin "1") (pinfunction "A_1") (pintype "unspecified"))
    )
    (net (code "19") (name "Net-(U1-E)") (class "Default")
      (node (ref "R7") (pin "2") (pinfunction "2_2") (pintype "input"))
      (node (ref "U1") (pin "3") (pinfunction "E_3") (pintype "unspecified"))
    )
    (net (code "20") (name "Net-(U2-FB)") (class "Default")
      (node (ref "C7") (pin "2") (pinfunction "2_2") (pintype "input"))
      (node (ref "R11") (pin "1") (pinfunction "1_1") (pintype "input"))
      (node (ref "R12") (pin "2") (pinfunction "2_2") (pintype "input"))
      (node (ref "U2") (pin "4") (pinfunction "FB_4") (pintype "unspecified"))
    )
    (net (code "21") (name "Net-(U4-ADJ)") (class "Default")
      (node (ref "R14") (pin "1") (pinfunction "1_1") (pintype "input"))
      (node (ref "R18") (pin "2") (pinfunction "2_2") (pintype "input"))
      (node (ref "U4") (pin "7") (pinfunction "ADJ_7") (pintype "unspecified"))
    )
    (net (code "22") (name "Net-(U4-CDELAY)") (class "Default")
      (node (ref "C23") (pin "2") (pinfunction "2_2") (pintype "unspecified"))
      (node (ref "R13") (pin "1") (pinfunction "1_1") (pintype "unspecified"))
      (node (ref "U4") (pin "5") (pinfunction "PWRGD_5") (pintype "unspecified"))
      (node (ref "U4") (pin "6") (pinfunction "CDELAY_6") (pintype "unspecified"))
    )
    (net (code "23") (name "Net-(U4-SHDN#)") (class "Default")
      (node (ref "R16") (pin "2") (pinfunction "2_2") (pintype "unspecified"))
      (node (ref "U4") (pin "3") (pinfunction "SHDN#_3") (pintype "unspecified"))
    )
    (net (code "24") (name "Net-(U5-EN)") (class "Default")
      (node (ref "R17") (pin "2") (pinfunction "2_2") (pintype "input"))
      (node (ref "U5") (pin "5") (pinfunction "EN_5") (pintype "unspecified"))
    )
    (net (code "25") (name "Net-(U5-FB)") (class "Default")
      (node (ref "R19") (pin "1") (pinfunction "1_1") (pintype "input"))
      (node (ref "R20") (pin "2") (pinfunction "2_2") (pintype "input"))
      (node (ref "U5") (pin "8") (pinfunction "FB_8") (pintype "unspecified"))
    )
    (net (code "26") (name "Net-(U5-PG)") (class "Default")
      (node (ref "R15") (pin "1") (pinfunction "1_1") (pintype "input"))
      (node (ref "U5") (pin "3") (pinfunction "PG_3") (pintype "unspecified"))
    )
    (net (code "27") (name "Net-(U5-SS)") (class "Default")
      (node (ref "C22") (pin "2") (pinfunction "2_2") (pintype "input"))
      (node (ref "U5") (pin "7") (pinfunction "SS_7") (pintype "unspecified"))
    )
    (net (code "28") (name "Net-(U6-EN)") (class "Default")
      (node (ref "C30") (pin "2") (pinfunction "2_2") (pintype "input"))
      (node (ref "R21") (pin "1") (pinfunction "1_1") (pintype "input"))
      (node (ref "U6") (pin "11") (pinfunction "EN_11") (pintype "unspecified"))
      (node (ref "U6") (pin "15") (pinfunction "SS_15") (pintype "unspecified"))
    )
    (net (code "29") (name "Net-(U6-PG)") (class "Default")
      (node (ref "R22") (pin "1") (pinfunction "1_1") (pintype "input"))
      (node (ref "U6") (pin "9") (pinfunction "PG_9") (pintype "unspecified"))
    )
    (net (code "30") (name "Net-(U7-EN)") (class "Default")
      (node (ref "C35") (pin "2") (pinfunction "2_2") (pintype "input"))
      (node (ref "R25") (pin "1") (pinfunction "1_1") (pintype "input"))
      (node (ref "U7") (pin "11") (pinfunction "EN_11") (pintype "unspecified"))
      (node (ref "U7") (pin "15") (pinfunction "SS_15") (pintype "unspecified"))
    )
    (net (code "31") (name "Net-(U7-PG)") (class "Default")
      (node (ref "R26") (pin "1") (pinfunction "1_1") (pintype "input"))
      (node (ref "U7") (pin "9") (pinfunction "PG_9") (pintype "unspecified"))
    )
    (net (code "32") (name "PGND") (class "Default")
      (node (ref "C6") (pin "2") (pinfunction "2_2") (pintype "unspecified"))
      (node (ref "R6") (pin "1") (pinfunction "1_1") (pintype "input"))
    )
    (net (code "33") (name "VCC_1.2") (class "Default")
      (node (ref "R21") (pin "2") (pinfunction "2_2") (pintype "input"))
      (node (ref "R23") (pin "1") (pinfunction "1_1") (pintype "input"))
      (node (ref "R24") (pin "2") (pinfunction "2_2") (pintype "input"))
      (node (ref "U6") (pin "16") (pinfunction "FB_16") (pintype "unspecified"))
    )
    (net (code "34") (name "VCC_1.2V") (class "Default")
      (node (ref "C24") (pin "2") (pinfunction "2_2") (pintype "input"))
      (node (ref "C25") (pin "1") (pinfunction "1_1") (pintype "input"))
      (node (ref "J9") (pin "1") (pinfunction "1_1") (pintype "unspecified"))
      (node (ref "R15") (pin "2") (pinfunction "2_2") (pintype "input"))
      (node (ref "R19") (pin "2") (pinfunction "2_2") (pintype "input"))
      (node (ref "R25") (pin "2") (pinfunction "2_2") (pintype "input"))
      (node (ref "R27") (pin "1") (pinfunction "1_1") (pintype "input"))
      (node (ref "R28") (pin "2") (pinfunction "2_2") (pintype "input"))
      (node (ref "U5") (pin "10") (pinfunction "OUT_10") (pintype "unspecified"))
      (node (ref "U5") (pin "9") (pinfunction "OUT_9") (pintype "unspecified"))
      (node (ref "U7") (pin "16") (pinfunction "FB_16") (pintype "unspecified"))
    )
    (net (code "35") (name "VCC_1.8V") (class "Default")
      (node (ref "C28") (pin "1") (pinfunction "1_1") (pintype "input"))
      (node (ref "C29") (pin "2") (pinfunction "2_2") (pintype "input"))
      (node (ref "J8") (pin "1") (pinfunction "1_1") (pintype "unspecified"))
      (node (ref "R22") (pin "2") (pinfunction "2_2") (pintype "input"))
      (node (ref "R23") (pin "2") (pinfunction "2_2") (pintype "input"))
      (node (ref "U6") (pin "1") (pinfunction "OUT_1") (pintype "unspecified"))
      (node (ref "U6") (pin "18") (pinfunction "OUT_18") (pintype "unspecified"))
      (node (ref "U6") (pin "19") (pinfunction "OUT_19") (pintype "unspecified"))
      (node (ref "U6") (pin "20") (pinfunction "OUT_20") (pintype "unspecified"))
    )
    (net (code "36") (name "VCC_2.5V") (class "Default")
      (node (ref "C33") (pin "1") (pinfunction "1_1") (pintype "input"))
      (node (ref "F3") (pin "2") (pinfunction "2_2") (pintype "input"))
      (node (ref "J7") (pin "1") (pinfunction "1_1") (pintype "unspecified"))
    )
    (net (code "37") (name "VCC_3.3V") (class "Default")
      (node (ref "C19") (pin "1") (pinfunction "1_1") (pintype "input"))
      (node (ref "F2") (pin "1") (pinfunction "1_1") (pintype "input"))
      (node (ref "R13") (pin "2") (pinfunction "2_2") (pintype "unspecified"))
      (node (ref "R14") (pin "2") (pinfunction "2_2") (pintype "input"))
      (node (ref "R17") (pin "1") (pinfunction "1_1") (pintype "input"))
      (node (ref "U4") (pin "8") (pinfunction "VOUT_8") (pintype "unspecified"))
    )
    (net (code "38") (name "VCC_3V3") (class "Default")
      (node (ref "C18") (pin "2") (pinfunction "2_2") (pintype "input"))
      (node (ref "F2") (pin "2") (pinfunction "2_2") (pintype "input"))
      (node (ref "J6") (pin "1") (pinfunction "1_1") (pintype "unspecified"))
    )
    (net (code "39") (name "VCC_5V") (class "Default")
      (node (ref "C10") (pin "1") (pinfunction "1_1") (pintype "input"))
      (node (ref "C17") (pin "1") (pinfunction "1_1") (pintype "input"))
      (node (ref "C20") (pin "2") (pinfunction "2_2") (pintype "input"))
      (node (ref "C21") (pin "2") (pinfunction "2_2") (pintype "input"))
      (node (ref "C26") (pin "2") (pinfunction "2_2") (pintype "input"))
      (node (ref "C27") (pin "2") (pinfunction "2_2") (pintype "input"))
      (node (ref "C31") (pin "2") (pinfunction "2_2") (pintype "input"))
      (node (ref "C32") (pin "2") (pinfunction "2_2") (pintype "input"))
      (node (ref "CN5") (pin "1") (pinfunction "1_1") (pintype "unspecified"))
      (node (ref "D6") (pin "1") (pinfunction "K_1") (pintype "input"))
      (node (ref "FL4") (pin "3") (pinfunction "OUT_3") (pintype "unspecified"))
      (node (ref "J5") (pin "1") (pinfunction "1_1") (pintype "unspecified"))
      (node (ref "R16") (pin "1") (pinfunction "1_1") (pintype "unspecified"))
      (node (ref "U4") (pin "1") (pinfunction "VIN_1") (pintype "unspecified"))
      (node (ref "U4") (pin "2") (pinfunction "VIN_2") (pintype "unspecified"))
      (node (ref "U5") (pin "1") (pinfunction "IN_1") (pintype "unspecified"))
      (node (ref "U5") (pin "2") (pinfunction "IN_2") (pintype "unspecified"))
      (node (ref "U5") (pin "4") (pinfunction "BIAS_4") (pintype "unspecified"))
      (node (ref "U6") (pin "10") (pinfunction "BIAS_10") (pintype "unspecified"))
      (node (ref "U6") (pin "5") (pinfunction "IN_5") (pintype "unspecified"))
      (node (ref "U6") (pin "6") (pinfunction "IN_6") (pintype "unspecified"))
      (node (ref "U6") (pin "7") (pinfunction "IN_7") (pintype "unspecified"))
      (node (ref "U6") (pin "8") (pinfunction "IN_8") (pintype "unspecified"))
      (node (ref "U7") (pin "10") (pinfunction "BIAS_10") (pintype "unspecified"))
      (node (ref "U7") (pin "5") (pinfunction "IN_5") (pintype "unspecified"))
      (node (ref "U7") (pin "6") (pinfunction "IN_6") (pintype "unspecified"))
      (node (ref "U7") (pin "7") (pinfunction "IN_7") (pintype "unspecified"))
      (node (ref "U7") (pin "8") (pinfunction "IN_8") (pintype "unspecified"))
    )
    (net (code "40") (name "VCC_7V") (class "Default")
      (node (ref "C14") (pin "1") (pinfunction "1_1") (pintype "input"))
      (node (ref "C9") (pin "1") (pinfunction "1_1") (pintype "input"))
      (node (ref "CN2") (pin "1") (pinfunction "1_1") (pintype "unspecified"))
      (node (ref "D5") (pin "1") (pinfunction "C_1") (pintype "unspecified"))
      (node (ref "FL3") (pin "3") (pinfunction "OUT_3") (pintype "unspecified"))
      (node (ref "J4") (pin "1") (pinfunction "1_1") (pintype "unspecified"))
      (node (ref "U3") (pin "1") (pinfunction "INPUT_1") (pintype "unspecified"))
    )
    (net (code "41") (name "VCC_12V") (class "Default")
      (node (ref "C2") (pin "1") (pinfunction "1_1") (pintype "unspecified"))
      (node (ref "C4") (pin "1") (pinfunction "1_1") (pintype "input"))
      (node (ref "C8") (pin "1") (pinfunction "1_1") (pintype "input"))
      (node (ref "CN1") (pin "1") (pinfunction "1_1") (pintype "unspecified"))
      (node (ref "J3") (pin "1") (pinfunction "1_1") (pintype "unspecified"))
      (node (ref "L1") (pin "2") (pinfunction "2_2") (pintype "unspecified"))
      (node (ref "R5") (pin "1") (pinfunction "1_1") (pintype "input"))
      (node (ref "U2") (pin "1") (pinfunction "VIN_1") (pintype "unspecified"))
    )
    (net (code "42") (name "unconnected-(U3-COMMON-Pad2)") (class "Default")
      (node (ref "U3") (pin "2") (pinfunction "COMMON_2") (pintype "unspecified"))
    )
  )
)
